# Sheet1.net
KiCad netlist of a schematic drawn in Altium Designer
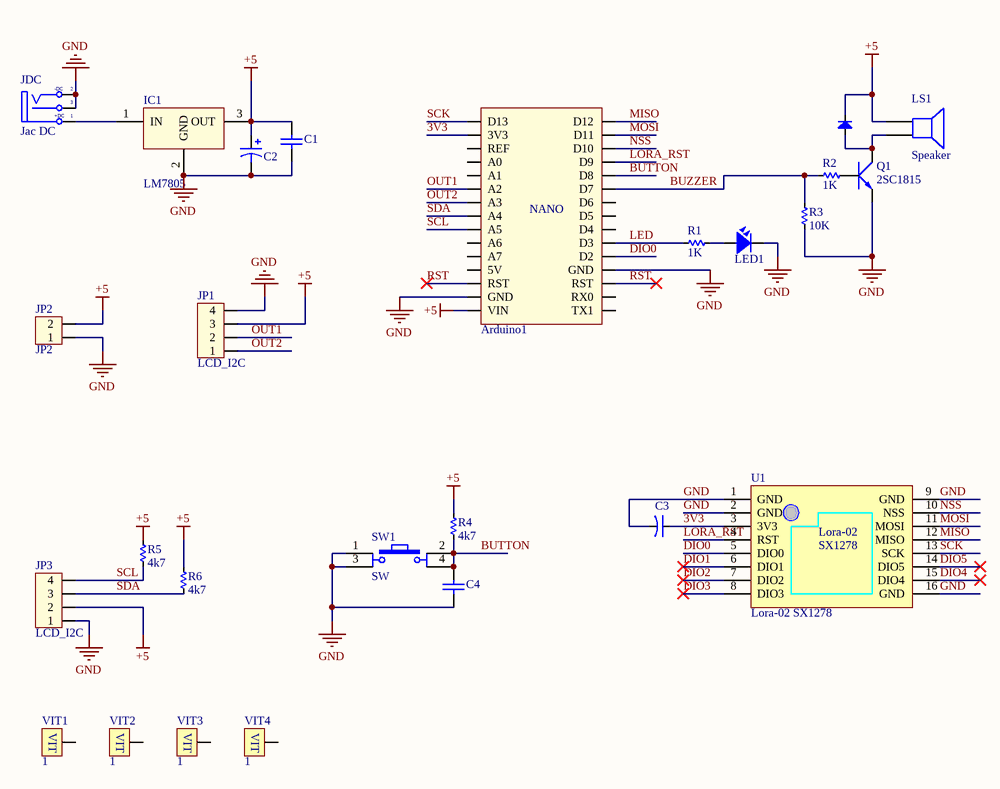
[diagram p0: Sheet1.SchDoc]

(export (version "E")
  (design (tool "Eeschema 10.0.6"))
  (components
    (comp (ref "Arduino1")
      (value "Arduino Nano")
      (footprint "Arduino Nano")
      (description "Arduino NANO")
      (libsource (lib "Thư Viện Altium FULL HD") (part "Arduino Nano"))
    )
    (comp (ref "C1")
      (value "Capacitor Ceramic")
      (footprint "C0805")
      (description "Capacitor")
      (fields (field (name "PUBLISHER") "Altium Limited"))
      (libsource (lib "My Library") (part "CapSMD"))
    )
    (comp (ref "C2")
      (value "Cap Pol 8mm")
      (footprint "C10mm")
      (description "Polarized Capacitor (Axial)")
      (fields (field (name "PUBLISHER") "Altium Limited"))
      (libsource (lib "My Library") (part "Cap Pol 8mm"))
    )
    (comp (ref "C3")
      (value "CN-ALU-DIP")
      (footprint "CA-ALU-5W")
      (description "Capacitor (Semiconductor SIM Model)")
      (fields (field (name "PUBLISHER") "Altium Limited"))
      (libsource (lib "Thư Viện Altium FULL HD") (part "CN-ALU-DIP"))
    )
    (comp (ref "C4")
      (value "Capacitor Ceramic")
      (footprint "C0805")
      (description "Capacitor")
      (fields (field (name "PUBLISHER") "Altium Limited"))
      (libsource (lib "My Library") (part "CapSMD"))
    )
    (comp (ref "DIO1")
      (value "Diode SMD")
      (footprint "DIO-SMD-106")
      (description "Default Diode")
      (fields (field (name "PUBLISHER") "Altium Limited"))
      (libsource (lib "My Library") (part "Diode SMD"))
    )
    (comp (ref "IC1")
      (value "LM7805")
      (footprint "QTO-220")
      (description "On ap +, from + 5 to + 24VDC")
      (libsource (lib "My Library") (part "LM78xx"))
    )
    (comp (ref "JDC")
      (value "Jac DC")
      (footprint "DC0")
      (description "Jac DC input")
      (libsource (lib "Thư Viện Altium FULL HD") (part "DCIN"))
    )
    (comp (ref "JP1")
      (value "LCD_I2C")
      (footprint "CON4")
      (description "Connector 4")
      (libsource (lib "My Library") (part "Con4"))
    )
    (comp (ref "JP2")
      (value "JP2")
      (footprint "CON2")
      (description "Connector 2")
      (libsource (lib "My Library") (part "Con2"))
    )
    (comp (ref "JP3")
      (value "LCD_I2C")
      (footprint "CON4")
      (description "Connector 4")
      (libsource (lib "My Library") (part "Con4"))
    )
    (comp (ref "LED1")
      (value "LED")
      (footprint "LED-3MM-YELLOW")
      (description "LED Single colour Green and Red")
      (libsource (lib "Thư Viện Altium FULL HD") (part "LED"))
    )
    (comp (ref "LS1")
      (value "Speaker")
      (footprint "SPEAKER")
      (description "Loudspeaker")
      (fields (field (name "PUBLISHER") "Altium Limited"))
      (libsource (lib "My Library") (part "Speaker"))
    )
    (comp (ref "Q1")
      (value "2SC1815")
      (footprint "TO92-123")
      (description "NPN 600mW, ECB")
      (libsource (lib "My Library") (part "2SC1815"))
    )
    (comp (ref "R1")
      (value "1K")
      (footprint "RES-SMD-1206")
      (description "Resistor")
      (fields
        (field (name "MANUFACTURER") "Generic Components")
        (field (name "PUBLISHER") "Altium Hobart Technology Centre")
      )
      (libsource (lib "Thư Viện Altium FULL HD") (part "Res-SMD"))
    )
    (comp (ref "R2")
      (value "1K")
      (footprint "RES-SMD-1206")
      (description "Resistor")
      (fields
        (field (name "MANUFACTURER") "Generic Components")
        (field (name "PUBLISHER") "Altium Hobart Technology Centre")
      )
      (libsource (lib "Thư Viện Altium FULL HD") (part "Res-SMD"))
    )
    (comp (ref "R3")
      (value "10K")
      (footprint "RES-SMD-1206")
      (description "Resistor")
      (fields
        (field (name "MANUFACTURER") "Generic Components")
        (field (name "PUBLISHER") "Altium Hobart Technology Centre")
      )
      (libsource (lib "Thư Viện Altium FULL HD") (part "Res-SMD"))
    )
    (comp (ref "R4")
      (value "4k7")
      (footprint "RES-SMD-1206")
      (description "Resistor")
      (fields
        (field (name "MANUFACTURER") "Generic Components")
        (field (name "PUBLISHER") "Altium Hobart Technology Centre")
      )
      (libsource (lib "Thư Viện Altium FULL HD") (part "Res-SMD"))
    )
    (comp (ref "R5")
      (value "4k7")
      (footprint "RES-SMD-1206")
      (description "Resistor")
      (fields
        (field (name "MANUFACTURER") "Generic Components")
        (field (name "PUBLISHER") "Altium Hobart Technology Centre")
      )
      (libsource (lib "Thư Viện Altium FULL HD") (part "Res-SMD"))
    )
    (comp (ref "R6")
      (value "4k7")
      (footprint "RES-SMD-1206")
      (description "Resistor")
      (fields
        (field (name "MANUFACTURER") "Generic Components")
        (field (name "PUBLISHER") "Altium Hobart Technology Centre")
      )
      (libsource (lib "Thư Viện Altium FULL HD") (part "Res-SMD"))
    )
    (comp (ref "SW1")
      (value "SW")
      (footprint "SW4")
      (description "Switch button 4 pin")
      (libsource (lib "My Library") (part "SW4"))
    )
    (comp (ref "U1")
      (value "Lora-02 SX1278")
      (footprint "Lora02-sx1278")
      (description "Lora-02 sx1278")
      (libsource (lib "Lora02-sx1278") (part "Lora-02 SX1278"))
    )
    (comp (ref "VIT1")
      (value "1")
      (footprint "VIT")
      (description "Oc Vit")
      (libsource (lib "My Library") (part "VIT"))
    )
    (comp (ref "VIT2")
      (value "1")
      (footprint "VIT")
      (description "Oc Vit")
      (libsource (lib "My Library") (part "VIT"))
    )
    (comp (ref "VIT3")
      (value "1")
      (footprint "VIT")
      (description "Oc Vit")
      (libsource (lib "My Library") (part "VIT"))
    )
    (comp (ref "VIT4")
      (value "1")
      (footprint "VIT")
      (description "Oc Vit")
      (libsource (lib "My Library") (part "VIT"))
    )
  )
  (nets
    (net (code "1") (name "+5") (class "Default")
      (node (ref "Arduino1") (pin "VIN") (pinfunction "VIN_VIN") (pintype "passive"))
      (node (ref "C1") (pin "2") (pinfunction "2_2") (pintype "passive"))
      (node (ref "C2") (pin "1") (pinfunction "1_1") (pintype "passive"))
      (node (ref "DIO1") (pin "2") (pinfunction "K_2") (pintype "passive"))
      (node (ref "IC1") (pin "3") (pinfunction "OUT_3") (pintype "passive"))
      (node (ref "JP1") (pin "3") (pinfunction "3_3") (pintype "passive"))
      (node (ref "JP2") (pin "2") (pinfunction "2_2") (pintype "passive"))
      (node (ref "JP3") (pin "2") (pinfunction "2_2") (pintype "passive"))
      (node (ref "LS1") (pin "1") (pinfunction "1_1") (pintype "passive"))
      (node (ref "R4") (pin "1") (pinfunction "1_1") (pintype "passive"))
      (node (ref "R5") (pin "1") (pinfunction "1_1") (pintype "passive"))
      (node (ref "R6") (pin "2") (pinfunction "2_2") (pintype "passive"))
    )
    (net (code "2") (name "/3V3") (class "Default")
      (node (ref "Arduino1") (pin "3V3") (pinfunction "3V3_3V3") (pintype "passive"))
      (node (ref "C3") (pin "1") (pinfunction "1_1") (pintype "passive"))
      (node (ref "U1") (pin "3") (pinfunction "3V3_3") (pintype "passive"))
    )
    (net (code "3") (name "/BUTTON") (class "Default")
      (node (ref "Arduino1") (pin "D8") (pinfunction "D8_D8") (pintype "passive"))
      (node (ref "C4") (pin "2") (pinfunction "2_2") (pintype "passive"))
      (node (ref "R4") (pin "2") (pinfunction "2_2") (pintype "passive"))
      (node (ref "SW1") (pin "2") (pintype "passive"))
      (node (ref "SW1") (pin "4") (pintype "passive"))
    )
    (net (code "4") (name "/BUZZER") (class "Default")
      (node (ref "Arduino1") (pin "D7") (pinfunction "D7_D7") (pintype "passive"))
      (node (ref "R2") (pin "1") (pinfunction "1_1") (pintype "passive"))
      (node (ref "R3") (pin "2") (pinfunction "2_2") (pintype "passive"))
    )
    (net (code "5") (name "/DIO0") (class "Default")
      (node (ref "Arduino1") (pin "D2") (pinfunction "D2_D2") (pintype "passive"))
      (node (ref "U1") (pin "5") (pinfunction "DIO0_5") (pintype "passive"))
    )
    (net (code "6") (name "/DIO1") (class "Default")
      (node (ref "U1") (pin "6") (pinfunction "DIO1_6") (pintype "passive+no_connect"))
    )
    (net (code "7") (name "/DIO2") (class "Default")
      (node (ref "U1") (pin "7") (pinfunction "DIO2_7") (pintype "passive+no_connect"))
    )
    (net (code "8") (name "/DIO3") (class "Default")
      (node (ref "U1") (pin "8") (pinfunction "DIO3_8") (pintype "passive+no_connect"))
    )
    (net (code "9") (name "/DIO4") (class "Default")
      (node (ref "U1") (pin "15") (pinfunction "DIO4_15") (pintype "passive+no_connect"))
    )
    (net (code "10") (name "/DIO5") (class "Default")
      (node (ref "U1") (pin "14") (pinfunction "DIO5_14") (pintype "passive+no_connect"))
    )
    (net (code "11") (name "/LED") (class "Default")
      (node (ref "Arduino1") (pin "D3") (pinfunction "D3_D3") (pintype "passive"))
      (node (ref "R1") (pin "1") (pinfunction "1_1") (pintype "passive"))
    )
    (net (code "12") (name "/LORA_RST") (class "Default")
      (node (ref "Arduino1") (pin "D9") (pinfunction "D9_D9") (pintype "passive"))
      (node (ref "U1") (pin "4") (pinfunction "RST_4") (pintype "passive"))
    )
    (net (code "13") (name "/MISO") (class "Default")
      (node (ref "Arduino1") (pin "D12") (pinfunction "D12_D12") (pintype "passive"))
      (node (ref "U1") (pin "12") (pinfunction "MISO_12") (pintype "passive"))
    )
    (net (code "14") (name "/MOSI") (class "Default")
      (node (ref "Arduino1") (pin "D11") (pinfunction "D11_D11") (pintype "passive"))
      (node (ref "U1") (pin "11") (pinfunction "MOSI_11") (pintype "passive"))
    )
    (net (code "15") (name "/NSS") (class "Default")
      (node (ref "Arduino1") (pin "D10") (pinfunction "D10_D10") (pintype "passive"))
      (node (ref "U1") (pin "10") (pinfunction "NSS_10") (pintype "passive"))
    )
    (net (code "16") (name "/OUT1") (class "Default")
      (node (ref "Arduino1") (pin "A2") (pinfunction "A2_A2") (pintype "passive"))
      (node (ref "JP1") (pin "2") (pinfunction "2_2") (pintype "passive"))
    )
    (net (code "17") (name "/OUT2") (class "Default")
      (node (ref "Arduino1") (pin "A3") (pinfunction "A3_A3") (pintype "passive"))
      (node (ref "JP1") (pin "1") (pinfunction "1_1") (pintype "passive"))
    )
    (net (code "18") (name "/RST") (class "Default")
      (node (ref "Arduino1") (pin "RST") (pinfunction "RST_RST") (pintype "passive+no_connect"))
    )
    (net (code "19") (name "/SCK") (class "Default")
      (node (ref "Arduino1") (pin "D13") (pinfunction "D13_D13") (pintype "passive"))
      (node (ref "U1") (pin "13") (pinfunction "SCK_13") (pintype "passive"))
    )
    (net (code "20") (name "/SCL") (class "Default")
      (node (ref "Arduino1") (pin "A5") (pinfunction "A5_A5") (pintype "passive"))
      (node (ref "JP3") (pin "4") (pinfunction "4_4") (pintype "passive"))
      (node (ref "R5") (pin "2") (pinfunction "2_2") (pintype "passive"))
    )
    (net (code "21") (name "/SDA") (class "Default")
      (node (ref "Arduino1") (pin "A4") (pinfunction "A4_A4") (pintype "passive"))
      (node (ref "JP3") (pin "3") (pinfunction "3_3") (pintype "passive"))
      (node (ref "R6") (pin "1") (pinfunction "1_1") (pintype "passive"))
    )
    (net (code "22") (name "GND") (class "Default")
      (node (ref "Arduino1") (pin "GND") (pinfunction "GND_GND") (pintype "passive"))
      (node (ref "C1") (pin "1") (pinfunction "1_1") (pintype "passive"))
      (node (ref "C2") (pin "2") (pinfunction "2_2") (pintype "passive"))
      (node (ref "C3") (pin "2") (pinfunction "2_2") (pintype "passive"))
      (node (ref "C4") (pin "1") (pinfunction "1_1") (pintype "passive"))
      (node (ref "IC1") (pin "2") (pinfunction "GND_2") (pintype "passive"))
      (node (ref "JDC") (pin "2") (pinfunction "TN_2") (pintype "passive"))
      (node (ref "JDC") (pin "3") (pinfunction "S_3") (pintype "power_in"))
      (node (ref "JP1") (pin "4") (pinfunction "4_4") (pintype "passive"))
      (node (ref "JP2") (pin "1") (pinfunction "1_1") (pintype "passive"))
      (node (ref "JP3") (pin "1") (pinfunction "1_1") (pintype "passive"))
      (node (ref "LED1") (pin "2") (pinfunction "2_2") (pintype "passive"))
      (node (ref "Q1") (pin "1") (pinfunction "E_1") (pintype "passive"))
      (node (ref "R3") (pin "1") (pinfunction "1_1") (pintype "passive"))
      (node (ref "SW1") (pin "1") (pintype "passive"))
      (node (ref "SW1") (pin "3") (pintype "passive"))
      (node (ref "U1") (pin "1") (pinfunction "GND_1") (pintype "passive"))
      (node (ref "U1") (pin "16") (pinfunction "GND_16") (pintype "passive"))
      (node (ref "U1") (pin "2") (pinfunction "GND_2") (pintype "passive"))
      (node (ref "U1") (pin "9") (pinfunction "GND_9") (pintype "passive"))
    )
    (net (code "23") (name "Net-(DIO1-A)") (class "Default")
      (node (ref "DIO1") (pin "1") (pinfunction "A_1") (pintype "passive"))
      (node (ref "LS1") (pin "2") (pinfunction "2_2") (pintype "passive"))
      (node (ref "Q1") (pin "2") (pinfunction "C_2") (pintype "passive"))
    )
    (net (code "24") (name "Net-(IC1-IN)") (class "Default")
      (node (ref "IC1") (pin "1") (pinfunction "IN_1") (pintype "passive"))
      (node (ref "JDC") (pin "1") (pinfunction "T_1") (pintype "passive"))
    )
    (net (code "25") (name "Net-(LED1-Pad1)") (class "Default")
      (node (ref "LED1") (pin "1") (pinfunction "1_1") (pintype "passive"))
      (node (ref "R1") (pin "2") (pinfunction "2_2") (pintype "passive"))
    )
    (net (code "26") (name "Net-(Q1-B)") (class "Default")
      (node (ref "Q1") (pin "3") (pinfunction "B_3") (pintype "passive"))
      (node (ref "R2") (pin "2") (pinfunction "2_2") (pintype "passive"))
    )
    (net (code "27") (name "unconnected-(Arduino1-Pad5V)") (class "Default")
      (node (ref "Arduino1") (pin "5V") (pinfunction "5V_5V") (pintype "passive"))
    )
    (net (code "28") (name "unconnected-(Arduino1-PadA0)") (class "Default")
      (node (ref "Arduino1") (pin "A0") (pinfunction "A0_A0") (pintype "passive"))
    )
    (net (code "29") (name "unconnected-(Arduino1-PadA1)") (class "Default")
      (node (ref "Arduino1") (pin "A1") (pinfunction "A1_A1") (pintype "passive"))
    )
    (net (code "30") (name "unconnected-(Arduino1-PadA6)") (class "Default")
      (node (ref "Arduino1") (pin "A6") (pinfunction "A6_A6") (pintype "passive"))
    )
    (net (code "31") (name "unconnected-(Arduino1-PadA7)") (class "Default")
      (node (ref "Arduino1") (pin "A7") (pinfunction "A7_A7") (pintype "passive"))
    )
    (net (code "32") (name "unconnected-(Arduino1-PadD4)") (class "Default")
      (node (ref "Arduino1") (pin "D4") (pinfunction "D4_D4") (pintype "passive"))
    )
    (net (code "33") (name "unconnected-(Arduino1-PadD5)") (class "Default")
      (node (ref "Arduino1") (pin "D5") (pinfunction "D5_D5") (pintype "passive"))
    )
    (net (code "34") (name "unconnected-(Arduino1-PadD6)") (class "Default")
      (node (ref "Arduino1") (pin "D6") (pinfunction "D6_D6") (pintype "passive"))
    )
    (net (code "35") (name "unconnected-(Arduino1-PadREF)") (class "Default")
      (node (ref "Arduino1") (pin "REF") (pinfunction "REF_REF") (pintype "passive"))
    )
    (net (code "36") (name "unconnected-(Arduino1-PadRX0)") (class "Default")
      (node (ref "Arduino1") (pin "RX0") (pinfunction "RX0_RX0") (pintype "passive"))
    )
    (net (code "37") (name "unconnected-(Arduino1-PadTX1)") (class "Default")
      (node (ref "Arduino1") (pin "TX1") (pinfunction "TX1_TX1") (pintype "passive"))
    )
    (net (code "38") (name "unconnected-(VIT1-1-PadVIT1)") (class "Default")
      (node (ref "VIT1") (pin "VIT1") (pinfunction "1_VIT1") (pintype "passive"))
    )
    (net (code "39") (name "unconnected-(VIT2-1-PadVIT1)") (class "Default")
      (node (ref "VIT2") (pin "VIT1") (pinfunction "1_VIT1") (pintype "passive"))
    )
    (net (code "40") (name "unconnected-(VIT3-1-PadVIT1)") (class "Default")
      (node (ref "VIT3") (pin "VIT1") (pinfunction "1_VIT1") (pintype "passive"))
    )
    (net (code "41") (name "unconnected-(VIT4-1-PadVIT1)") (class "Default")
      (node (ref "VIT4") (pin "VIT1") (pinfunction "1_VIT1") (pintype "passive"))
    )
  )
)
